# ec.net
KiCad netlist of a schematic drawn in EAGLE
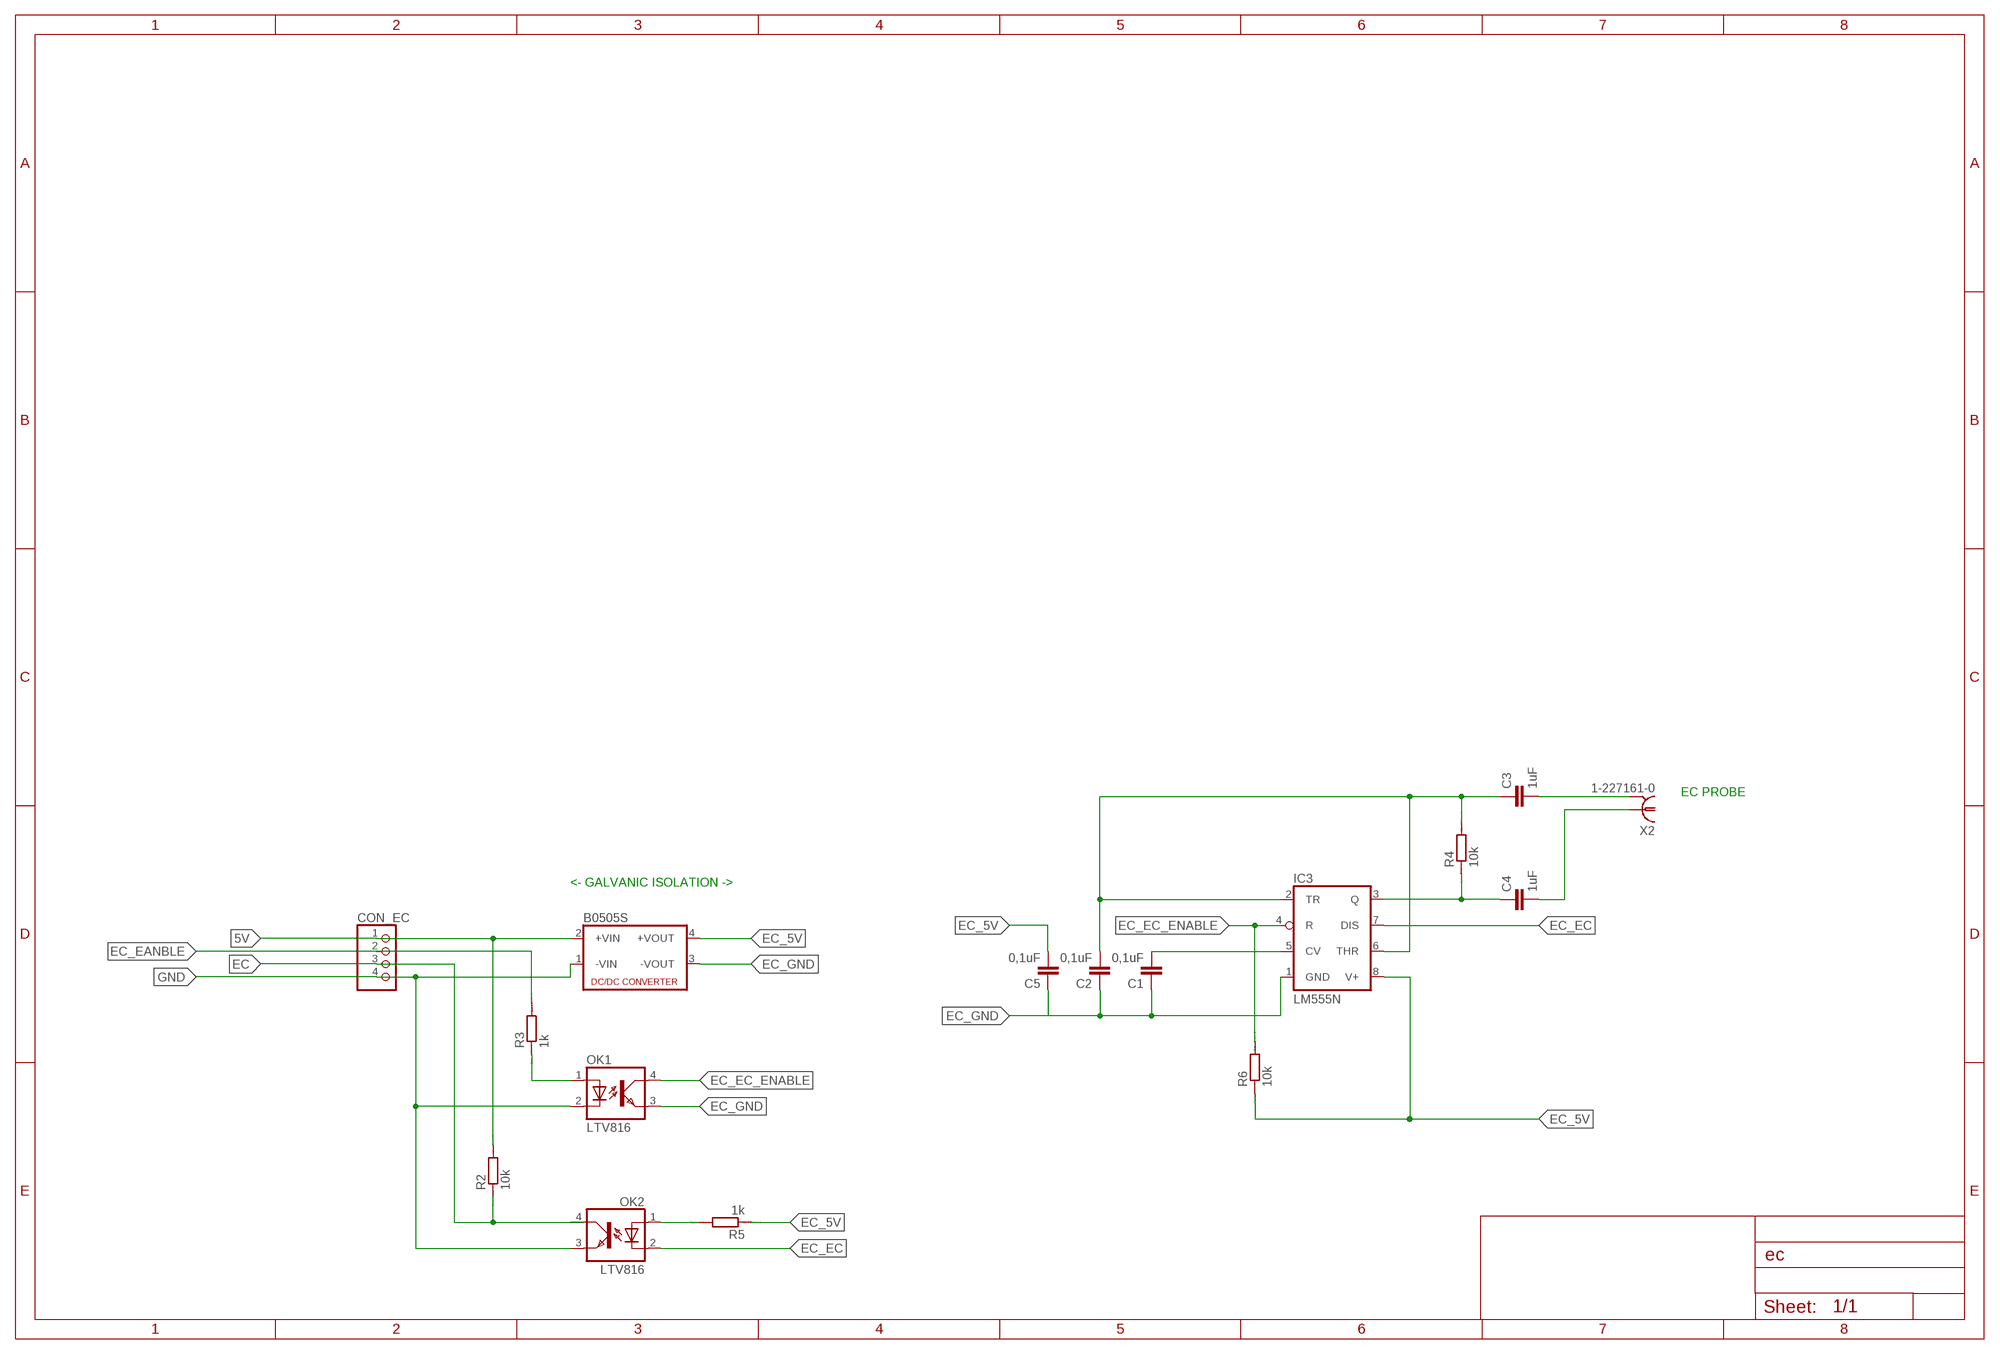
[diagram p0: schematic, sheet 1]

(export (version "E")
  (design (tool "Eeschema 10.0.6"))
  (components
    (comp (ref "B0505S")
      (value "NME")
      (footprint "eagle-import:NME")
      (fields (field (name "MF") "C & D TECHNOLOGIES, INC") (field (name "MPN") "NME1205D"))
      (libsource (lib "eagle-import") (part "NME"))
    )
    (comp (ref "C1")
      (value "0,1uF")
      (footprint "eagle-import:C050-024X044")
      (libsource (lib "eagle-import") (part "C-EU050-024X044"))
    )
    (comp (ref "C2")
      (value "0,1uF")
      (footprint "eagle-import:C050-024X044")
      (libsource (lib "eagle-import") (part "C-EU050-024X044"))
    )
    (comp (ref "C3")
      (value "1uF")
      (footprint "eagle-import:C050-024X044")
      (libsource (lib "eagle-import") (part "C-EU050-024X044"))
    )
    (comp (ref "C4")
      (value "1uF")
      (footprint "eagle-import:C050-024X044")
      (libsource (lib "eagle-import") (part "C-EU050-024X044"))
    )
    (comp (ref "C5")
      (value "0,1uF")
      (footprint "eagle-import:C050-024X044")
      (libsource (lib "eagle-import") (part "C-EU050-024X044"))
    )
    (comp (ref "CON_EC")
      (value "PINHD-1X4")
      (footprint "eagle-import:1X04")
      (libsource (lib "eagle-import") (part "PINHD-1X4"))
    )
    (comp (ref "IC3")
      (value "LM555N")
      (footprint "eagle-import:DIL08")
      (libsource (lib "eagle-import") (part "555NLM"))
    )
    (comp (ref "OK1")
      (value "LTV816")
      (footprint "eagle-import:DIL04")
      (libsource (lib "eagle-import") (part "LTV816"))
    )
    (comp (ref "OK2")
      (value "LTV816")
      (footprint "eagle-import:DIL04")
      (libsource (lib "eagle-import") (part "LTV816"))
    )
    (comp (ref "R2")
      (value "10k")
      (footprint "eagle-import:0207_10")
      (libsource (lib "eagle-import") (part "R0207/10"))
    )
    (comp (ref "R3")
      (value "1k")
      (footprint "eagle-import:0207_10")
      (libsource (lib "eagle-import") (part "R0207/10"))
    )
    (comp (ref "R4")
      (value "10k")
      (footprint "eagle-import:0207_10")
      (libsource (lib "eagle-import") (part "R0207/10"))
    )
    (comp (ref "R5")
      (value "1k")
      (footprint "eagle-import:0207_10")
      (libsource (lib "eagle-import") (part "R0207/10"))
    )
    (comp (ref "R6")
      (value "10k")
      (footprint "eagle-import:0207_10")
      (libsource (lib "eagle-import") (part "R0207/10"))
    )
    (comp (ref "X2")
      (value "1-227161-0")
      (footprint "eagle-import:AMP_227161")
      (fields (field (name "MF") "TYCO ELECTRONICS") (field (name "MPN") "1-227161"))
      (libsource (lib "eagle-import") (part "?2271611--0"))
    )
  )
  (nets
    (net (code "1") (name "5V") (class "Default")
      (node (ref "B0505S") (pin "2") (pinfunction "+VIN_2") (pintype "passive"))
      (node (ref "CON_EC") (pin "1") (pinfunction "1_1") (pintype "passive"))
      (node (ref "R2") (pin "2") (pinfunction "2_2") (pintype "passive"))
    )
    (net (code "2") (name "EC") (class "Default")
      (node (ref "CON_EC") (pin "3") (pinfunction "3_3") (pintype "passive"))
      (node (ref "OK2") (pin "4") (pinfunction "COL_4") (pintype "passive"))
      (node (ref "R2") (pin "1") (pinfunction "1_1") (pintype "passive"))
    )
    (net (code "3") (name "EC_5V") (class "Default")
      (node (ref "B0505S") (pin "4") (pinfunction "+VOUT_4") (pintype "passive"))
      (node (ref "C5") (pin "2") (pinfunction "2_2") (pintype "passive"))
      (node (ref "IC3") (pin "8") (pinfunction "V+_8") (pintype "power_in"))
      (node (ref "R5") (pin "1") (pinfunction "1_1") (pintype "passive"))
      (node (ref "R6") (pin "1") (pinfunction "1_1") (pintype "passive"))
    )
    (net (code "4") (name "EC_EANBLE") (class "Default")
      (node (ref "CON_EC") (pin "2") (pinfunction "2_2") (pintype "passive"))
      (node (ref "R3") (pin "2") (pinfunction "2_2") (pintype "passive"))
    )
    (net (code "5") (name "EC_EC") (class "Default")
      (node (ref "IC3") (pin "7") (pinfunction "DIS_7") (pintype "input"))
      (node (ref "OK2") (pin "2") (pinfunction "C_2") (pintype "passive"))
    )
    (net (code "6") (name "EC_EC_ENABLE") (class "Default")
      (node (ref "IC3") (pin "4") (pinfunction "R_4") (pintype "input"))
      (node (ref "OK1") (pin "4") (pinfunction "COL_4") (pintype "passive"))
      (node (ref "R6") (pin "2") (pinfunction "2_2") (pintype "passive"))
    )
    (net (code "7") (name "EC_GND") (class "Default")
      (node (ref "B0505S") (pin "3") (pinfunction "-VOUT_3") (pintype "passive"))
      (node (ref "C1") (pin "1") (pinfunction "1_1") (pintype "passive"))
      (node (ref "C2") (pin "1") (pinfunction "1_1") (pintype "passive"))
      (node (ref "C5") (pin "1") (pinfunction "1_1") (pintype "passive"))
      (node (ref "IC3") (pin "1") (pinfunction "GND_1") (pintype "power_in"))
      (node (ref "OK1") (pin "3") (pinfunction "EMIT_3") (pintype "passive"))
    )
    (net (code "8") (name "GND") (class "Default")
      (node (ref "B0505S") (pin "1") (pinfunction "-VIN_1") (pintype "passive"))
      (node (ref "CON_EC") (pin "4") (pinfunction "4_4") (pintype "passive"))
      (node (ref "OK1") (pin "2") (pinfunction "C_2") (pintype "passive"))
      (node (ref "OK2") (pin "3") (pinfunction "EMIT_3") (pintype "passive"))
    )
    (net (code "9") (name "Net-(C3-Pad2)") (class "Default")
      (node (ref "C3") (pin "2") (pinfunction "2_2") (pintype "passive"))
      (node (ref "X2") (pin "2") (pinfunction "2_2") (pintype "passive"))
    )
    (net (code "10") (name "Net-(C4-Pad2)") (class "Default")
      (node (ref "C4") (pin "2") (pinfunction "2_2") (pintype "passive"))
      (node (ref "X2") (pin "1") (pinfunction "1_1") (pintype "passive"))
    )
    (net (code "11") (name "Net-(IC3-CV)") (class "Default")
      (node (ref "C1") (pin "2") (pinfunction "2_2") (pintype "passive"))
      (node (ref "IC3") (pin "5") (pinfunction "CV_5") (pintype "input"))
    )
    (net (code "12") (name "Net-(IC3-Q)") (class "Default")
      (node (ref "C4") (pin "1") (pinfunction "1_1") (pintype "passive"))
      (node (ref "IC3") (pin "3") (pinfunction "Q_3") (pintype "output"))
      (node (ref "R4") (pin "1") (pinfunction "1_1") (pintype "passive"))
    )
    (net (code "13") (name "Net-(IC3-THR)") (class "Default")
      (node (ref "C2") (pin "2") (pinfunction "2_2") (pintype "passive"))
      (node (ref "C3") (pin "1") (pinfunction "1_1") (pintype "passive"))
      (node (ref "IC3") (pin "2") (pinfunction "TR_2") (pintype "input"))
      (node (ref "IC3") (pin "6") (pinfunction "THR_6") (pintype "input"))
      (node (ref "R4") (pin "2") (pinfunction "2_2") (pintype "passive"))
    )
    (net (code "14") (name "Net-(OK1-A)") (class "Default")
      (node (ref "OK1") (pin "1") (pinfunction "A_1") (pintype "passive"))
      (node (ref "R3") (pin "1") (pinfunction "1_1") (pintype "passive"))
    )
    (net (code "15") (name "Net-(OK2-A)") (class "Default")
      (node (ref "OK2") (pin "1") (pinfunction "A_1") (pintype "passive"))
      (node (ref "R5") (pin "2") (pinfunction "2_2") (pintype "passive"))
    )
  )
)
